# Switch_board_left.net
KiCad netlist of a schematic drawn in Altium Designer
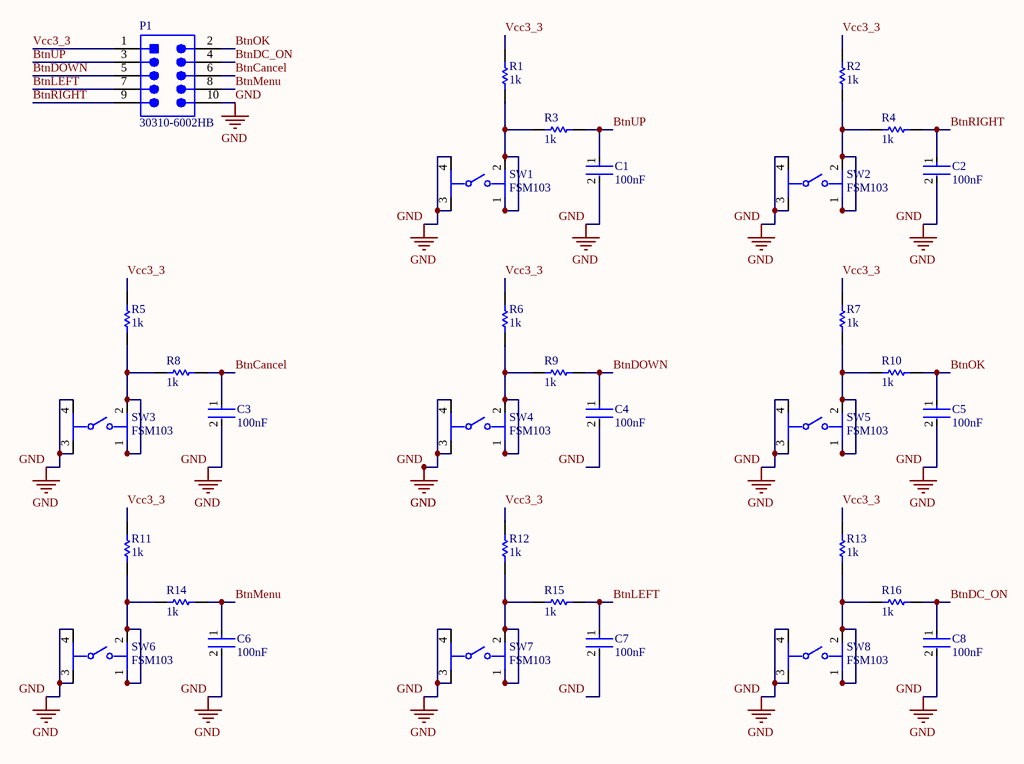
[diagram p0: Switch_board_left.SchDoc]

(export (version "E")
  (design (tool "Eeschema 10.0.6"))
  (components
    (comp (ref "C1")
      (value "100nF")
      (footprint "FP-0805-L_2_01_0_2-W_1_25-IPC_B")
      (description "General Purpose Ceramic Capacitor, 0805, 100nF, 10%, X7R, 15%, 100V")
      (fields (field (name "VOLTAGE") "100V") (field (name "TOLERANCE") "10%"))
      (libsource (lib "Altium Content Vault") (part "b4654b650e69147ec39a6b967a45e02"))
    )
    (comp (ref "C2")
      (value "100nF")
      (footprint "FP-0805-L_2_01_0_2-W_1_25-IPC_B")
      (description "General Purpose Ceramic Capacitor, 0805, 100nF, 10%, X7R, 15%, 100V")
      (fields (field (name "VOLTAGE") "100V") (field (name "TOLERANCE") "10%"))
      (libsource (lib "Altium Content Vault") (part "b4654b650e69147ec39a6b967a45e02"))
    )
    (comp (ref "C3")
      (value "100nF")
      (footprint "FP-0805-L_2_01_0_2-W_1_25-IPC_B")
      (description "General Purpose Ceramic Capacitor, 0805, 100nF, 10%, X7R, 15%, 100V")
      (fields (field (name "VOLTAGE") "100V") (field (name "TOLERANCE") "10%"))
      (libsource (lib "Altium Content Vault") (part "b4654b650e69147ec39a6b967a45e02"))
    )
    (comp (ref "C4")
      (value "100nF")
      (footprint "FP-0805-L_2_01_0_2-W_1_25-IPC_B")
      (description "General Purpose Ceramic Capacitor, 0805, 100nF, 10%, X7R, 15%, 100V")
      (fields (field (name "VOLTAGE") "100V") (field (name "TOLERANCE") "10%"))
      (libsource (lib "Altium Content Vault") (part "b4654b650e69147ec39a6b967a45e02"))
    )
    (comp (ref "C5")
      (value "100nF")
      (footprint "FP-0805-L_2_01_0_2-W_1_25-IPC_B")
      (description "General Purpose Ceramic Capacitor, 0805, 100nF, 10%, X7R, 15%, 100V")
      (fields (field (name "VOLTAGE") "100V") (field (name "TOLERANCE") "10%"))
      (libsource (lib "Altium Content Vault") (part "b4654b650e69147ec39a6b967a45e02"))
    )
    (comp (ref "C6")
      (value "100nF")
      (footprint "FP-0805-L_2_01_0_2-W_1_25-IPC_B")
      (description "General Purpose Ceramic Capacitor, 0805, 100nF, 10%, X7R, 15%, 100V")
      (fields (field (name "VOLTAGE") "100V") (field (name "TOLERANCE") "10%"))
      (libsource (lib "Altium Content Vault") (part "b4654b650e69147ec39a6b967a45e02"))
    )
    (comp (ref "C7")
      (value "100nF")
      (footprint "FP-0805-L_2_01_0_2-W_1_25-IPC_B")
      (description "General Purpose Ceramic Capacitor, 0805, 100nF, 10%, X7R, 15%, 100V")
      (fields (field (name "VOLTAGE") "100V") (field (name "TOLERANCE") "10%"))
      (libsource (lib "Altium Content Vault") (part "b4654b650e69147ec39a6b967a45e02"))
    )
    (comp (ref "C8")
      (value "100nF")
      (footprint "FP-0805-L_2_01_0_2-W_1_25-IPC_B")
      (description "General Purpose Ceramic Capacitor, 0805, 100nF, 10%, X7R, 15%, 100V")
      (fields (field (name "VOLTAGE") "100V") (field (name "TOLERANCE") "10%"))
      (libsource (lib "Altium Content Vault") (part "b4654b650e69147ec39a6b967a45e02"))
    )
    (comp (ref "P1")
      (value "30310-6002HB")
      (footprint "3M-30310-6002HB-10_V")
      (fields (field (name "MANUFACTURER") "3M"))
      (libsource (lib "Altium Content Vault") (part "CN-2P-M-R10"))
    )
    (comp (ref "R1")
      (value "1k")
      (footprint "RESC2013X50X30LL20T20")
      (fields (field (name "MANUFACTURER") "Vishay Dale") (field (name "PART NUMBER") "CRCW08050000Z0EA"))
      (libsource (lib "Altium Content Vault") (part "RES"))
    )
    (comp (ref "R2")
      (value "1k")
      (footprint "RESC2013X50X30LL20T20")
      (fields (field (name "MANUFACTURER") "Vishay Dale") (field (name "PART NUMBER") "CRCW08050000Z0EA"))
      (libsource (lib "Altium Content Vault") (part "RES"))
    )
    (comp (ref "R3")
      (value "1k")
      (footprint "RESC2013X50X30LL20T20")
      (fields (field (name "MANUFACTURER") "Vishay Dale") (field (name "PART NUMBER") "CRCW08050000Z0EA"))
      (libsource (lib "Altium Content Vault") (part "RES"))
    )
    (comp (ref "R4")
      (value "1k")
      (footprint "RESC2013X50X30LL20T20")
      (fields (field (name "MANUFACTURER") "Vishay Dale") (field (name "PART NUMBER") "CRCW08050000Z0EA"))
      (libsource (lib "Altium Content Vault") (part "RES"))
    )
    (comp (ref "R5")
      (value "1k")
      (footprint "RESC2013X50X30LL20T20")
      (fields (field (name "MANUFACTURER") "Vishay Dale") (field (name "PART NUMBER") "CRCW08050000Z0EA"))
      (libsource (lib "Altium Content Vault") (part "RES"))
    )
    (comp (ref "R6")
      (value "1k")
      (footprint "RESC2013X50X30LL20T20")
      (fields (field (name "MANUFACTURER") "Vishay Dale") (field (name "PART NUMBER") "CRCW08050000Z0EA"))
      (libsource (lib "Altium Content Vault") (part "RES"))
    )
    (comp (ref "R7")
      (value "1k")
      (footprint "RESC2013X50X30LL20T20")
      (fields (field (name "MANUFACTURER") "Vishay Dale") (field (name "PART NUMBER") "CRCW08050000Z0EA"))
      (libsource (lib "Altium Content Vault") (part "RES"))
    )
    (comp (ref "R8")
      (value "1k")
      (footprint "RESC2013X50X30LL20T20")
      (fields (field (name "MANUFACTURER") "Vishay Dale") (field (name "PART NUMBER") "CRCW08050000Z0EA"))
      (libsource (lib "Altium Content Vault") (part "RES"))
    )
    (comp (ref "R9")
      (value "1k")
      (footprint "RESC2013X50X30LL20T20")
      (fields (field (name "MANUFACTURER") "Vishay Dale") (field (name "PART NUMBER") "CRCW08050000Z0EA"))
      (libsource (lib "Altium Content Vault") (part "RES"))
    )
    (comp (ref "R10")
      (value "1k")
      (footprint "RESC2013X50X30LL20T20")
      (fields (field (name "MANUFACTURER") "Vishay Dale") (field (name "PART NUMBER") "CRCW08050000Z0EA"))
      (libsource (lib "Altium Content Vault") (part "RES"))
    )
    (comp (ref "R11")
      (value "1k")
      (footprint "RESC2013X50X30LL20T20")
      (fields (field (name "MANUFACTURER") "Vishay Dale") (field (name "PART NUMBER") "CRCW08050000Z0EA"))
      (libsource (lib "Altium Content Vault") (part "RES"))
    )
    (comp (ref "R12")
      (value "1k")
      (footprint "RESC2013X50X30LL20T20")
      (fields (field (name "MANUFACTURER") "Vishay Dale") (field (name "PART NUMBER") "CRCW08050000Z0EA"))
      (libsource (lib "Altium Content Vault") (part "RES"))
    )
    (comp (ref "R13")
      (value "1k")
      (footprint "RESC2013X50X30LL20T20")
      (fields (field (name "MANUFACTURER") "Vishay Dale") (field (name "PART NUMBER") "CRCW08050000Z0EA"))
      (libsource (lib "Altium Content Vault") (part "RES"))
    )
    (comp (ref "R14")
      (value "1k")
      (footprint "RESC2013X50X30LL20T20")
      (fields (field (name "MANUFACTURER") "Vishay Dale") (field (name "PART NUMBER") "CRCW08050000Z0EA"))
      (libsource (lib "Altium Content Vault") (part "RES"))
    )
    (comp (ref "R15")
      (value "1k")
      (footprint "RESC2013X50X30LL20T20")
      (fields (field (name "MANUFACTURER") "Vishay Dale") (field (name "PART NUMBER") "CRCW08050000Z0EA"))
      (libsource (lib "Altium Content Vault") (part "RES"))
    )
    (comp (ref "R16")
      (value "1k")
      (footprint "RESC2013X50X30LL20T20")
      (fields (field (name "MANUFACTURER") "Vishay Dale") (field (name "PART NUMBER") "CRCW08050000Z0EA"))
      (libsource (lib "Altium Content Vault") (part "RES"))
    )
    (comp (ref "SW1")
      (value "FSM103")
      (footprint "FP-FSM103-MFG")
      (description "SWITCH TACTILE SPST-NO 0.05A 24V")
      (libsource (lib "Altium Content Vault") (part "c0df99d12937e9d2da15afdedf14b17"))
    )
    (comp (ref "SW2")
      (value "FSM103")
      (footprint "FP-FSM103-MFG")
      (description "SWITCH TACTILE SPST-NO 0.05A 24V")
      (libsource (lib "Altium Content Vault") (part "c0df99d12937e9d2da15afdedf14b17"))
    )
    (comp (ref "SW3")
      (value "FSM103")
      (footprint "FP-FSM103-MFG")
      (description "SWITCH TACTILE SPST-NO 0.05A 24V")
      (libsource (lib "Altium Content Vault") (part "c0df99d12937e9d2da15afdedf14b17"))
    )
    (comp (ref "SW4")
      (value "FSM103")
      (footprint "FP-FSM103-MFG")
      (description "SWITCH TACTILE SPST-NO 0.05A 24V")
      (libsource (lib "Altium Content Vault") (part "c0df99d12937e9d2da15afdedf14b17"))
    )
    (comp (ref "SW5")
      (value "FSM103")
      (footprint "FP-FSM103-MFG")
      (description "SWITCH TACTILE SPST-NO 0.05A 24V")
      (libsource (lib "Altium Content Vault") (part "c0df99d12937e9d2da15afdedf14b17"))
    )
    (comp (ref "SW6")
      (value "FSM103")
      (footprint "FP-FSM103-MFG")
      (description "SWITCH TACTILE SPST-NO 0.05A 24V")
      (libsource (lib "Altium Content Vault") (part "c0df99d12937e9d2da15afdedf14b17"))
    )
    (comp (ref "SW7")
      (value "FSM103")
      (footprint "FP-FSM103-MFG")
      (description "SWITCH TACTILE SPST-NO 0.05A 24V")
      (libsource (lib "Altium Content Vault") (part "c0df99d12937e9d2da15afdedf14b17"))
    )
    (comp (ref "SW8")
      (value "FSM103")
      (footprint "FP-FSM103-MFG")
      (description "SWITCH TACTILE SPST-NO 0.05A 24V")
      (libsource (lib "Altium Content Vault") (part "c0df99d12937e9d2da15afdedf14b17"))
    )
  )
  (nets
    (net (code "1") (name "/BtnCancel") (class "Default")
      (node (ref "C3") (pin "1") (pinfunction "1_1") (pintype "passive"))
      (node (ref "P1") (pin "6") (pinfunction "6_6") (pintype "passive"))
      (node (ref "R8") (pin "1") (pinfunction "1_1") (pintype "passive"))
    )
    (net (code "2") (name "/BtnDC_ON") (class "Default")
      (node (ref "C8") (pin "1") (pinfunction "1_1") (pintype "passive"))
      (node (ref "P1") (pin "4") (pinfunction "4_4") (pintype "passive"))
      (node (ref "R16") (pin "1") (pinfunction "1_1") (pintype "passive"))
    )
    (net (code "3") (name "/BtnDOWN") (class "Default")
      (node (ref "C4") (pin "1") (pinfunction "1_1") (pintype "passive"))
      (node (ref "P1") (pin "5") (pinfunction "5_5") (pintype "passive"))
      (node (ref "R9") (pin "1") (pinfunction "1_1") (pintype "passive"))
    )
    (net (code "4") (name "/BtnLEFT") (class "Default")
      (node (ref "C7") (pin "1") (pinfunction "1_1") (pintype "passive"))
      (node (ref "P1") (pin "7") (pinfunction "7_7") (pintype "passive"))
      (node (ref "R15") (pin "1") (pinfunction "1_1") (pintype "passive"))
    )
    (net (code "5") (name "/BtnMenu") (class "Default")
      (node (ref "C6") (pin "1") (pinfunction "1_1") (pintype "passive"))
      (node (ref "P1") (pin "8") (pinfunction "8_8") (pintype "passive"))
      (node (ref "R14") (pin "1") (pinfunction "1_1") (pintype "passive"))
    )
    (net (code "6") (name "/BtnOK") (class "Default")
      (node (ref "C5") (pin "1") (pinfunction "1_1") (pintype "passive"))
      (node (ref "P1") (pin "2") (pinfunction "2_2") (pintype "passive"))
      (node (ref "R10") (pin "1") (pinfunction "1_1") (pintype "passive"))
    )
    (net (code "7") (name "/BtnRIGHT") (class "Default")
      (node (ref "C2") (pin "1") (pinfunction "1_1") (pintype "passive"))
      (node (ref "P1") (pin "9") (pinfunction "9_9") (pintype "passive"))
      (node (ref "R4") (pin "1") (pinfunction "1_1") (pintype "passive"))
    )
    (net (code "8") (name "/BtnUP") (class "Default")
      (node (ref "C1") (pin "1") (pinfunction "1_1") (pintype "passive"))
      (node (ref "P1") (pin "3") (pinfunction "3_3") (pintype "passive"))
      (node (ref "R3") (pin "1") (pinfunction "1_1") (pintype "passive"))
    )
    (net (code "9") (name "/Vcc3_3") (class "Default")
      (node (ref "P1") (pin "1") (pinfunction "1_1") (pintype "passive"))
      (node (ref "R1") (pin "2") (pinfunction "2_2") (pintype "passive"))
      (node (ref "R11") (pin "2") (pinfunction "2_2") (pintype "passive"))
      (node (ref "R12") (pin "2") (pinfunction "2_2") (pintype "passive"))
      (node (ref "R13") (pin "2") (pinfunction "2_2") (pintype "passive"))
      (node (ref "R2") (pin "2") (pinfunction "2_2") (pintype "passive"))
      (node (ref "R5") (pin "2") (pinfunction "2_2") (pintype "passive"))
      (node (ref "R6") (pin "2") (pinfunction "2_2") (pintype "passive"))
      (node (ref "R7") (pin "2") (pinfunction "2_2") (pintype "passive"))
    )
    (net (code "10") (name "GND") (class "Default")
      (node (ref "C1") (pin "2") (pinfunction "2_2") (pintype "passive"))
      (node (ref "C2") (pin "2") (pinfunction "2_2") (pintype "passive"))
      (node (ref "C3") (pin "2") (pinfunction "2_2") (pintype "passive"))
      (node (ref "C4") (pin "2") (pinfunction "2_2") (pintype "passive"))
      (node (ref "C5") (pin "2") (pinfunction "2_2") (pintype "passive"))
      (node (ref "C6") (pin "2") (pinfunction "2_2") (pintype "passive"))
      (node (ref "C7") (pin "2") (pinfunction "2_2") (pintype "passive"))
      (node (ref "C8") (pin "2") (pinfunction "2_2") (pintype "passive"))
      (node (ref "P1") (pin "10") (pinfunction "10_10") (pintype "passive"))
      (node (ref "SW1") (pin "3") (pinfunction "3_3") (pintype "passive"))
      (node (ref "SW1") (pin "4") (pinfunction "4_4") (pintype "passive"))
      (node (ref "SW2") (pin "3") (pinfunction "3_3") (pintype "passive"))
      (node (ref "SW2") (pin "4") (pinfunction "4_4") (pintype "passive"))
      (node (ref "SW3") (pin "3") (pinfunction "3_3") (pintype "passive"))
      (node (ref "SW3") (pin "4") (pinfunction "4_4") (pintype "passive"))
      (node (ref "SW4") (pin "3") (pinfunction "3_3") (pintype "passive"))
      (node (ref "SW4") (pin "4") (pinfunction "4_4") (pintype "passive"))
      (node (ref "SW5") (pin "3") (pinfunction "3_3") (pintype "passive"))
      (node (ref "SW5") (pin "4") (pinfunction "4_4") (pintype "passive"))
      (node (ref "SW6") (pin "3") (pinfunction "3_3") (pintype "passive"))
      (node (ref "SW6") (pin "4") (pinfunction "4_4") (pintype "passive"))
      (node (ref "SW7") (pin "3") (pinfunction "3_3") (pintype "passive"))
      (node (ref "SW7") (pin "4") (pinfunction "4_4") (pintype "passive"))
      (node (ref "SW8") (pin "3") (pinfunction "3_3") (pintype "passive"))
      (node (ref "SW8") (pin "4") (pinfunction "4_4") (pintype "passive"))
    )
    (net (code "11") (name "Net-(R1-Pad1)") (class "Default")
      (node (ref "R1") (pin "1") (pinfunction "1_1") (pintype "passive"))
      (node (ref "R3") (pin "2") (pinfunction "2_2") (pintype "passive"))
      (node (ref "SW1") (pin "1") (pinfunction "1_1") (pintype "passive"))
      (node (ref "SW1") (pin "2") (pinfunction "2_2") (pintype "passive"))
    )
    (net (code "12") (name "Net-(R2-Pad1)") (class "Default")
      (node (ref "R2") (pin "1") (pinfunction "1_1") (pintype "passive"))
      (node (ref "R4") (pin "2") (pinfunction "2_2") (pintype "passive"))
      (node (ref "SW2") (pin "1") (pinfunction "1_1") (pintype "passive"))
      (node (ref "SW2") (pin "2") (pinfunction "2_2") (pintype "passive"))
    )
    (net (code "13") (name "Net-(R5-Pad1)") (class "Default")
      (node (ref "R5") (pin "1") (pinfunction "1_1") (pintype "passive"))
      (node (ref "R8") (pin "2") (pinfunction "2_2") (pintype "passive"))
      (node (ref "SW3") (pin "1") (pinfunction "1_1") (pintype "passive"))
      (node (ref "SW3") (pin "2") (pinfunction "2_2") (pintype "passive"))
    )
    (net (code "14") (name "Net-(R6-Pad1)") (class "Default")
      (node (ref "R6") (pin "1") (pinfunction "1_1") (pintype "passive"))
      (node (ref "R9") (pin "2") (pinfunction "2_2") (pintype "passive"))
      (node (ref "SW4") (pin "1") (pinfunction "1_1") (pintype "passive"))
      (node (ref "SW4") (pin "2") (pinfunction "2_2") (pintype "passive"))
    )
    (net (code "15") (name "Net-(R10-Pad2)") (class "Default")
      (node (ref "R10") (pin "2") (pinfunction "2_2") (pintype "passive"))
      (node (ref "R7") (pin "1") (pinfunction "1_1") (pintype "passive"))
      (node (ref "SW5") (pin "1") (pinfunction "1_1") (pintype "passive"))
      (node (ref "SW5") (pin "2") (pinfunction "2_2") (pintype "passive"))
    )
    (net (code "16") (name "Net-(R11-Pad1)") (class "Default")
      (node (ref "R11") (pin "1") (pinfunction "1_1") (pintype "passive"))
      (node (ref "R14") (pin "2") (pinfunction "2_2") (pintype "passive"))
      (node (ref "SW6") (pin "1") (pinfunction "1_1") (pintype "passive"))
      (node (ref "SW6") (pin "2") (pinfunction "2_2") (pintype "passive"))
    )
    (net (code "17") (name "Net-(R12-Pad1)") (class "Default")
      (node (ref "R12") (pin "1") (pinfunction "1_1") (pintype "passive"))
      (node (ref "R15") (pin "2") (pinfunction "2_2") (pintype "passive"))
      (node (ref "SW7") (pin "1") (pinfunction "1_1") (pintype "passive"))
      (node (ref "SW7") (pin "2") (pinfunction "2_2") (pintype "passive"))
    )
    (net (code "18") (name "Net-(R13-Pad1)") (class "Default")
      (node (ref "R13") (pin "1") (pinfunction "1_1") (pintype "passive"))
      (node (ref "R16") (pin "2") (pinfunction "2_2") (pintype "passive"))
      (node (ref "SW8") (pin "1") (pinfunction "1_1") (pintype "passive"))
      (node (ref "SW8") (pin "2") (pinfunction "2_2") (pintype "passive"))
    )
  )
)
